# timer.net
KiCad netlist of a schematic drawn in EAGLE
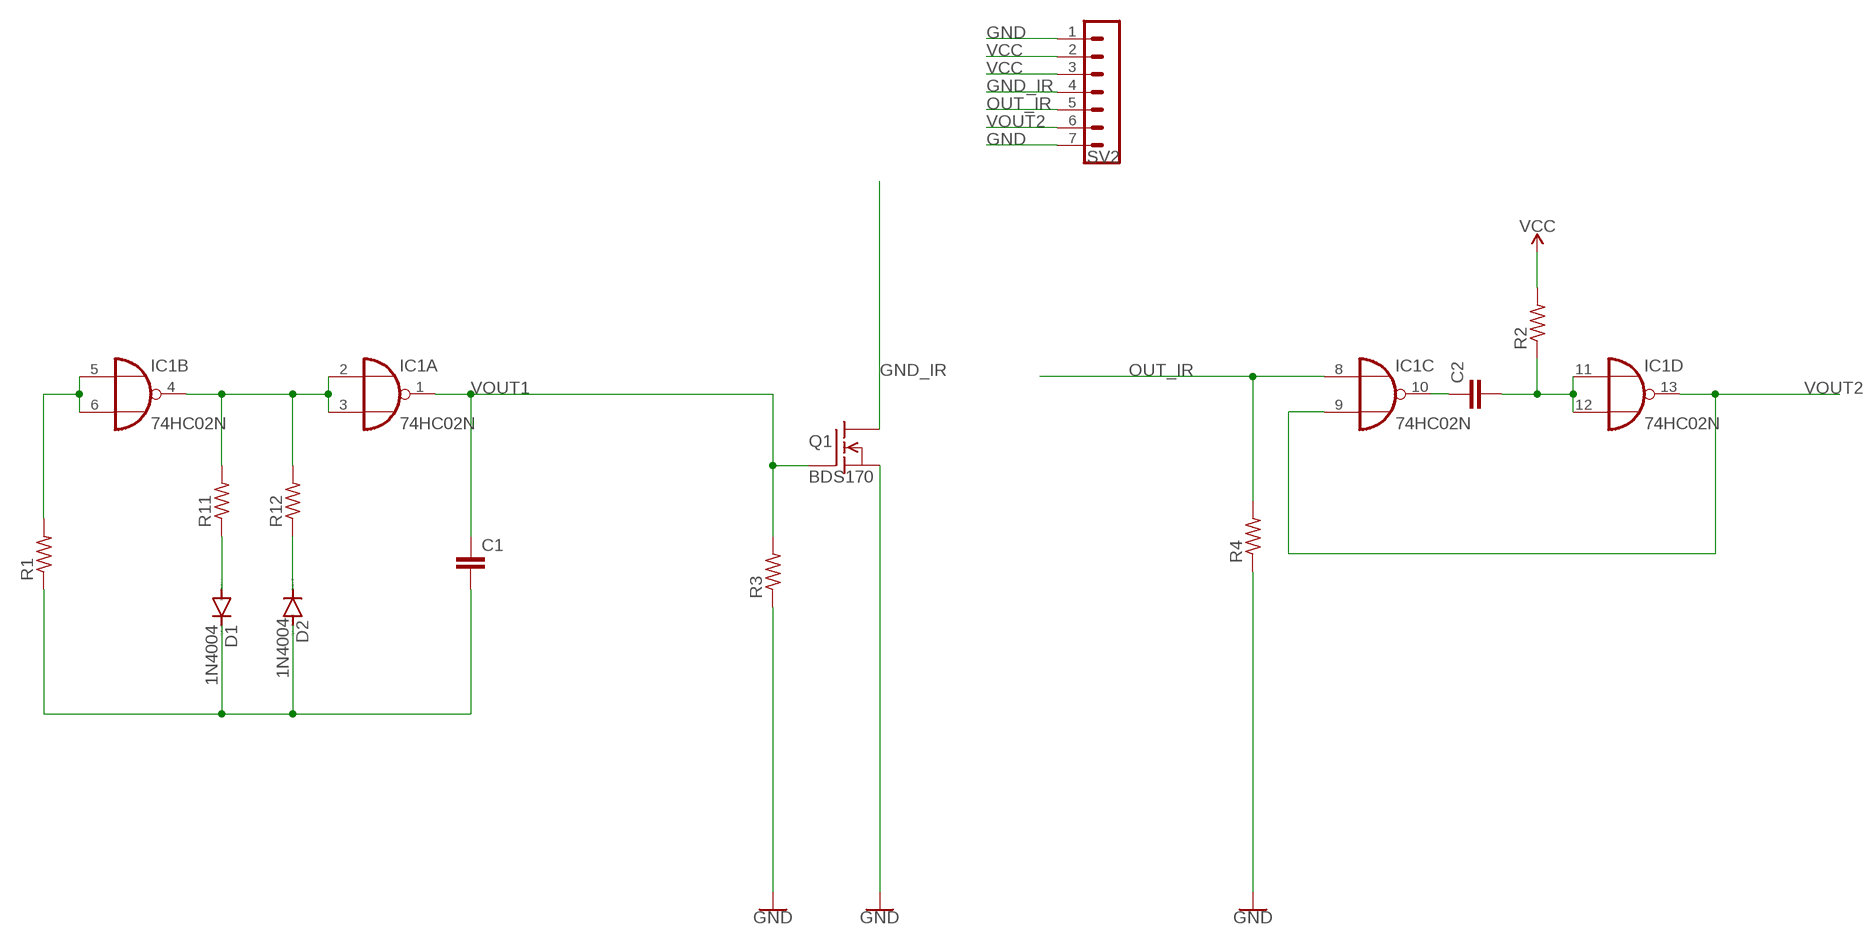
[diagram p0: schematic, sheet 1]

(export (version "E")
  (design (tool "Eeschema 10.0.6"))
  (components
    (comp (ref "C1")
      (value "C-EU025-024X044")
      (footprint "eagle-import:C025-024X044")
      (libsource (lib "eagle-import") (part "C-EU025-024X044"))
    )
    (comp (ref "C2")
      (value "C-EU050-025X075")
      (footprint "eagle-import:C050-025X075")
      (libsource (lib "eagle-import") (part "C-EU050-025X075"))
    )
    (comp (ref "D1")
      (value "1N4004")
      (footprint "eagle-import:DO41-10")
      (libsource (lib "eagle-import") (part "1N4004"))
    )
    (comp (ref "D2")
      (value "1N4004")
      (footprint "eagle-import:DO41-10")
      (libsource (lib "eagle-import") (part "1N4004"))
    )
    (comp (ref "IC1")
      (value "74HC02N")
      (footprint "eagle-import:DIL14")
      (libsource (lib "eagle-import") (part "7402NHC"))
    )
    (comp (ref "Q1")
      (value "VN10KM")
      (footprint "eagle-import:TO92-")
      (libsource (lib "eagle-import") (part "VN10KM"))
    )
    (comp (ref "R1")
      (value "R-US_0207/10")
      (footprint "eagle-import:0207_10")
      (libsource (lib "eagle-import") (part "R-US_0207/10"))
    )
    (comp (ref "R2")
      (value "R-US_0207/10")
      (footprint "eagle-import:0207_10")
      (libsource (lib "eagle-import") (part "R-US_0207/10"))
    )
    (comp (ref "R3")
      (value "R-US_0207/10")
      (footprint "eagle-import:0207_10")
      (libsource (lib "eagle-import") (part "R-US_0207/10"))
    )
    (comp (ref "R4")
      (value "R-US_0207/10")
      (footprint "eagle-import:0207_10")
      (libsource (lib "eagle-import") (part "R-US_0207/10"))
    )
    (comp (ref "R11")
      (value "R-US_0207/10")
      (footprint "eagle-import:0207_10")
      (libsource (lib "eagle-import") (part "R-US_0207/10"))
    )
    (comp (ref "R12")
      (value "R-US_0207/10")
      (footprint "eagle-import:0207_10")
      (libsource (lib "eagle-import") (part "R-US_0207/10"))
    )
    (comp (ref "SV2")
      (value "MA07-1")
      (footprint "eagle-import:MA07-1")
      (libsource (lib "eagle-import") (part "MA07-1"))
    )
  )
  (nets
    (net (code "1") (name "/GND_IR") (class "Default")
      (node (ref "Q1") (pin "1") (pinfunction "D_1") (pintype "passive"))
      (node (ref "SV2") (pin "4") (pinfunction "4_4") (pintype "passive"))
    )
    (net (code "2") (name "/OUT_IR") (class "Default")
      (node (ref "IC1") (pin "8") (pinfunction "I0_8") (pintype "input"))
      (node (ref "R4") (pin "2") (pinfunction "2_2") (pintype "passive"))
      (node (ref "SV2") (pin "5") (pinfunction "5_5") (pintype "passive"))
    )
    (net (code "3") (name "/VOUT1") (class "Default")
      (node (ref "C1") (pin "1") (pinfunction "1_1") (pintype "passive"))
      (node (ref "IC1") (pin "1") (pinfunction "O_1") (pintype "output"))
      (node (ref "Q1") (pin "2") (pinfunction "G_2") (pintype "passive"))
      (node (ref "R3") (pin "2") (pinfunction "2_2") (pintype "passive"))
    )
    (net (code "4") (name "/VOUT2") (class "Default")
      (node (ref "IC1") (pin "13") (pinfunction "O_13") (pintype "output"))
      (node (ref "IC1") (pin "9") (pinfunction "I1_9") (pintype "input"))
      (node (ref "SV2") (pin "6") (pinfunction "6_6") (pintype "passive"))
    )
    (net (code "5") (name "GND") (class "Default")
      (node (ref "Q1") (pin "3") (pinfunction "S_3") (pintype "passive"))
      (node (ref "R3") (pin "1") (pinfunction "1_1") (pintype "passive"))
      (node (ref "R4") (pin "1") (pinfunction "1_1") (pintype "passive"))
      (node (ref "SV2") (pin "1") (pinfunction "1_1") (pintype "passive"))
      (node (ref "SV2") (pin "7") (pinfunction "7_7") (pintype "passive"))
    )
    (net (code "6") (name "Net-(C1-Pad2)") (class "Default")
      (node (ref "C1") (pin "2") (pinfunction "2_2") (pintype "passive"))
      (node (ref "D1") (pin "C") (pinfunction "C_C") (pintype "passive"))
      (node (ref "D2") (pin "A") (pinfunction "A_A") (pintype "passive"))
      (node (ref "R1") (pin "1") (pinfunction "1_1") (pintype "passive"))
    )
    (net (code "7") (name "Net-(D1-PadA)") (class "Default")
      (node (ref "D1") (pin "A") (pinfunction "A_A") (pintype "passive"))
      (node (ref "R11") (pin "1") (pinfunction "1_1") (pintype "passive"))
    )
    (net (code "8") (name "Net-(D2-PadC)") (class "Default")
      (node (ref "D2") (pin "C") (pinfunction "C_C") (pintype "passive"))
      (node (ref "R12") (pin "1") (pinfunction "1_1") (pintype "passive"))
    )
    (net (code "9") (name "Net-(IC1A-I0)") (class "Default")
      (node (ref "IC1") (pin "2") (pinfunction "I0_2") (pintype "input"))
      (node (ref "IC1") (pin "3") (pinfunction "I1_3") (pintype "input"))
      (node (ref "IC1") (pin "4") (pinfunction "O_4") (pintype "output"))
      (node (ref "R11") (pin "2") (pinfunction "2_2") (pintype "passive"))
      (node (ref "R12") (pin "2") (pinfunction "2_2") (pintype "passive"))
    )
    (net (code "10") (name "Net-(IC1B-I0)") (class "Default")
      (node (ref "IC1") (pin "5") (pinfunction "I0_5") (pintype "input"))
      (node (ref "IC1") (pin "6") (pinfunction "I1_6") (pintype "input"))
      (node (ref "R1") (pin "2") (pinfunction "2_2") (pintype "passive"))
    )
    (net (code "11") (name "Net-(IC1C-O)") (class "Default")
      (node (ref "C2") (pin "1") (pinfunction "1_1") (pintype "passive"))
      (node (ref "IC1") (pin "10") (pinfunction "O_10") (pintype "output"))
    )
    (net (code "12") (name "Net-(IC1D-I0)") (class "Default")
      (node (ref "C2") (pin "2") (pinfunction "2_2") (pintype "passive"))
      (node (ref "IC1") (pin "11") (pinfunction "I0_11") (pintype "input"))
      (node (ref "IC1") (pin "12") (pinfunction "I1_12") (pintype "input"))
      (node (ref "R2") (pin "1") (pinfunction "1_1") (pintype "passive"))
    )
    (net (code "13") (name "VCC") (class "Default")
      (node (ref "R2") (pin "2") (pinfunction "2_2") (pintype "passive"))
      (node (ref "SV2") (pin "2") (pinfunction "2_2") (pintype "passive"))
      (node (ref "SV2") (pin "3") (pinfunction "3_3") (pintype "passive"))
    )
  )
)
